# NRF52840.net
KiCad netlist of a schematic drawn in Altium Designer
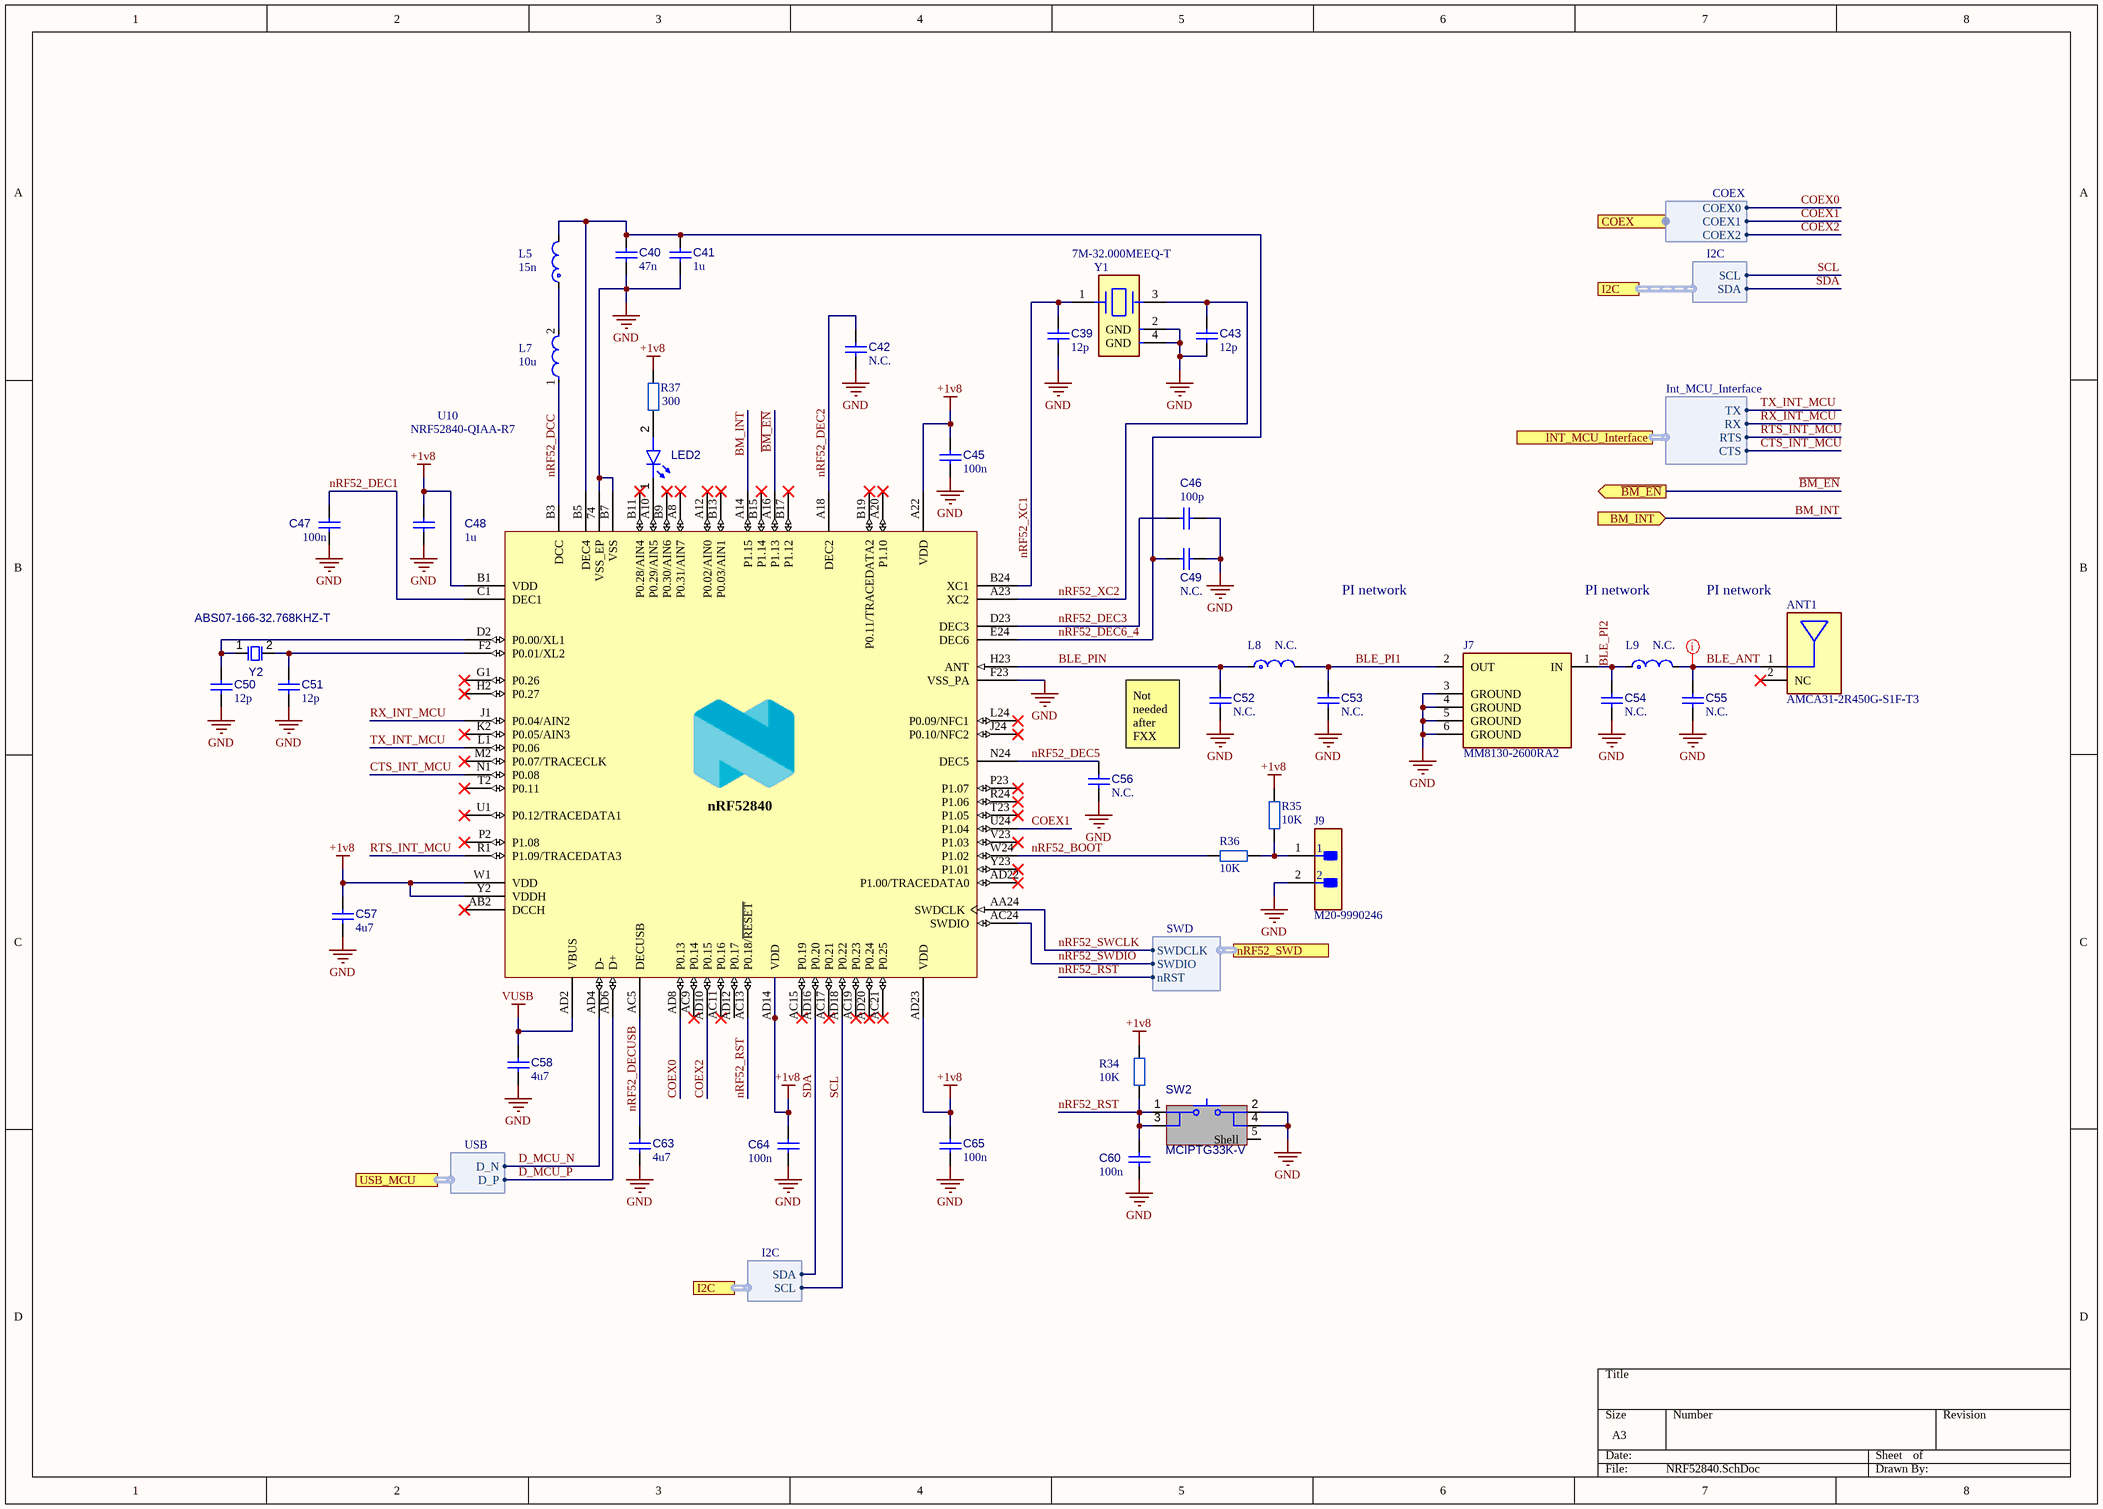
[diagram p0: NRF52840.SchDoc]

(export (version "E")
  (design (tool "Eeschema 10.0.6"))
  (components
    (comp (ref "ANT1")
      (value "AMCA31-2R450G-S1F-T3")
      (footprint "FP-AMCA31-MFG")
      (description "RF ANT 2.4GHZ CHIP SOLDER SMD")
      (fields
        (field (name "OCTOPART") "https://octopart.com/amca31-2r450g-s1f-t3-abracon-31435383")
        (field (name "MANUFACTURER") "Abracon")
      )
      (libsource (lib "Altium Content Vault") (part "feefd54aed95757a858c12fc87bd8d5"))
    )
    (comp (ref "C39")
      (value "12p")
      (footprint "CAPC1005X55X25LL05T10 HD")
      (description "Chip Capacitor, 0402 (1005 Metric)")
      (fields (field (name "TOLERANCE") "?%") (field (name "Comment") "Capacitor 0402"))
      (libsource (lib "Motonaut") (part "CAP-NP-2"))
    )
    (comp (ref "C40")
      (value "47n")
      (footprint "CAPC1005X55X25LL05T10 HD")
      (description "Chip Capacitor, 0402 (1005 Metric)")
      (fields (field (name "TOLERANCE") "?%") (field (name "Comment") "Capacitor 0402"))
      (libsource (lib "Motonaut") (part "CAP-NP-2"))
    )
    (comp (ref "C41")
      (value "1u")
      (footprint "CAPC1005X55X25LL05T10 HD")
      (description "Chip Capacitor, 0402 (1005 Metric)")
      (fields (field (name "TOLERANCE") "?%") (field (name "Comment") "Capacitor 0402"))
      (libsource (lib "Motonaut") (part "CAP-NP-2"))
    )
    (comp (ref "C42")
      (value "N.C.")
      (footprint "CAPC1005X55X25LL05T10 HD")
      (description "Chip Capacitor, 0402 (1005 Metric)")
      (fields (field (name "TOLERANCE") "?%") (field (name "Comment") "Capacitor 0402"))
      (libsource (lib "Motonaut") (part "CAP-NP-2"))
    )
    (comp (ref "C43")
      (value "12p")
      (footprint "CAPC1005X55X25LL05T10 HD")
      (description "Chip Capacitor, 0402 (1005 Metric)")
      (fields (field (name "TOLERANCE") "?%") (field (name "Comment") "Capacitor 0402"))
      (libsource (lib "Motonaut") (part "CAP-NP-2"))
    )
    (comp (ref "C45")
      (value "100n")
      (footprint "CAPC1005X55X25LL05T10 HD")
      (description "Chip Capacitor, 0402 (1005 Metric)")
      (fields (field (name "TOLERANCE") "?%") (field (name "Comment") "Capacitor 0402"))
      (libsource (lib "Motonaut") (part "CAP-NP-2"))
    )
    (comp (ref "C46")
      (value "100p")
      (footprint "CAPC1005X55X25LL05T10 HD")
      (description "Chip Capacitor, 0402 (1005 Metric)")
      (fields (field (name "TOLERANCE") "?%") (field (name "Comment") "Capacitor 0402"))
      (libsource (lib "Motonaut") (part "CAP-NP-2"))
    )
    (comp (ref "C47")
      (value "100n")
      (footprint "CAPC1005X55X25LL05T10 HD")
      (description "Chip Capacitor, 0402 (1005 Metric)")
      (fields (field (name "TOLERANCE") "?%") (field (name "Comment") "Capacitor 0402"))
      (libsource (lib "Motonaut") (part "CAP-NP-2"))
    )
    (comp (ref "C48")
      (value "1u")
      (footprint "CAPC1005X55X25LL05T10 HD")
      (description "Chip Capacitor, 0402 (1005 Metric)")
      (fields (field (name "TOLERANCE") "?%") (field (name "Comment") "Capacitor 0402"))
      (libsource (lib "Motonaut") (part "CAP-NP-2"))
    )
    (comp (ref "C49")
      (value "N.C.")
      (footprint "CAPC1005X55X25LL05T10 HD")
      (description "Chip Capacitor, 0402 (1005 Metric)")
      (fields (field (name "TOLERANCE") "?%") (field (name "Comment") "Capacitor 0402"))
      (libsource (lib "Motonaut") (part "CAP-NP-2"))
    )
    (comp (ref "C50")
      (value "12p")
      (footprint "CAPC1005X55X25LL05T10 HD")
      (description "Chip Capacitor, 0402 (1005 Metric)")
      (fields (field (name "TOLERANCE") "?%") (field (name "Comment") "Capacitor 0402"))
      (libsource (lib "Motonaut") (part "CAP-NP-2"))
    )
    (comp (ref "C51")
      (value "12p")
      (footprint "CAPC1005X55X25LL05T10 HD")
      (description "Chip Capacitor, 0402 (1005 Metric)")
      (fields (field (name "TOLERANCE") "?%") (field (name "Comment") "Capacitor 0402"))
      (libsource (lib "Motonaut") (part "CAP-NP-2"))
    )
    (comp (ref "C52")
      (value "N.C.")
      (footprint "CAPC1005X55X25LL05T10 HD")
      (description "Chip Capacitor, 0402 (1005 Metric)")
      (fields (field (name "TOLERANCE") "?%") (field (name "Comment") "Capacitor 0402"))
      (libsource (lib "Motonaut") (part "CAP-NP-2"))
    )
    (comp (ref "C53")
      (value "N.C.")
      (footprint "CAPC1005X55X25LL05T10 HD")
      (description "Chip Capacitor, 0402 (1005 Metric)")
      (fields (field (name "TOLERANCE") "?%") (field (name "Comment") "Capacitor 0402"))
      (libsource (lib "Motonaut") (part "CAP-NP-2"))
    )
    (comp (ref "C54")
      (value "N.C.")
      (footprint "CAPC1005X55X25LL05T10 HD")
      (description "Chip Capacitor, 0402 (1005 Metric)")
      (fields (field (name "TOLERANCE") "?%") (field (name "Comment") "Capacitor 0402"))
      (libsource (lib "Motonaut") (part "CAP-NP-2"))
    )
    (comp (ref "C55")
      (value "N.C.")
      (footprint "CAPC1005X55X25LL05T10 HD")
      (description "Chip Capacitor, 0402 (1005 Metric)")
      (fields (field (name "TOLERANCE") "?%") (field (name "Comment") "Capacitor 0402"))
      (libsource (lib "Motonaut") (part "CAP-NP-2"))
    )
    (comp (ref "C56")
      (value "N.C.")
      (footprint "CAPC1005X55X25LL05T10 HD")
      (description "Chip Capacitor, 0402 (1005 Metric)")
      (fields (field (name "TOLERANCE") "?%") (field (name "Comment") "Capacitor 0402"))
      (libsource (lib "Motonaut") (part "CAP-NP-2"))
    )
    (comp (ref "C57")
      (value "4u7")
      (footprint "CAPC1005X55X25LL05T10 HD")
      (description "Chip Capacitor, 0402 (1005 Metric)")
      (fields (field (name "TOLERANCE") "?%") (field (name "Comment") "Capacitor 0402"))
      (libsource (lib "Motonaut") (part "CAP-NP-2"))
    )
    (comp (ref "C58")
      (value "4u7")
      (footprint "CAPC1005X55X25LL05T10 HD")
      (description "Chip Capacitor, 0402 (1005 Metric)")
      (fields (field (name "TOLERANCE") "?%") (field (name "Comment") "Capacitor 0402"))
      (libsource (lib "Motonaut") (part "CAP-NP-2"))
    )
    (comp (ref "C60")
      (value "100n")
      (footprint "CAPC1005X55X25LL05T10 HD")
      (description "Chip Capacitor, 0402 (1005 Metric)")
      (fields (field (name "TOLERANCE") "?%") (field (name "Comment") "Capacitor 0402"))
      (libsource (lib "Motonaut") (part "CAP-NP-2"))
    )
    (comp (ref "C63")
      (value "4u7")
      (footprint "CAPC1005X55X25LL05T10 HD")
      (description "Chip Capacitor, 0402 (1005 Metric)")
      (fields (field (name "TOLERANCE") "?%") (field (name "Comment") "Capacitor 0402"))
      (libsource (lib "Motonaut") (part "CAP-NP-2"))
    )
    (comp (ref "C64")
      (value "100n")
      (footprint "CAPC1005X55X25LL05T10 HD")
      (description "Chip Capacitor, 0402 (1005 Metric)")
      (fields (field (name "TOLERANCE") "?%") (field (name "Comment") "Capacitor 0402"))
      (libsource (lib "Motonaut") (part "CAP-NP-2"))
    )
    (comp (ref "C65")
      (value "100n")
      (footprint "CAPC1005X55X25LL05T10 HD")
      (description "Chip Capacitor, 0402 (1005 Metric)")
      (fields (field (name "TOLERANCE") "?%") (field (name "Comment") "Capacitor 0402"))
      (libsource (lib "Motonaut") (part "CAP-NP-2"))
    )
    (comp (ref "J7")
      (value "MM8130-2600RA2")
      (footprint "FP-MM8130-2600RA2-MFG")
      (description "CONN SWF JACK STR 50 OHM SMD")
      (libsource (lib "Motonaut") (part "77d6c4703912e83beb04a2353eb46e6"))
    )
    (comp (ref "J9")
      (value "M20-9990246")
      (footprint "FP-M20-9990246-MFG")
      (description "CONN HEADER VERT 2POS 2.54MM")
      (fields
        (field (name "OCTOPART") "https://octopart.com/m20-9990246-harwin-2590635")
        (field (name "MANUFACTURER") "Harwin")
      )
      (libsource (lib "Altium Content Vault") (part "3bc925449376181038e59eaffc5286c"))
    )
    (comp (ref "L5")
      (value "15n")
      (footprint "INDC1005X55X25LL05T10_A")
      (description "Inductor RF Chip Thin Film 0402")
      (fields (field (name "Comment") "Inductor 0402"))
      (libsource (lib "Motonaut") (part "4cc4b267dca4c8e51f7102f422741d8"))
    )
    (comp (ref "L7")
      (value "10u")
      (footprint "FP-LQM18DN_70-MFG")
      (description "Inductor 0603 Multilayer")
      (fields (field (name "Comment") "Inductor 0603"))
      (libsource (lib "Motonaut") (part "725321dda6339637d4d059423bc1c3c"))
    )
    (comp (ref "L8")
      (value "N.C.")
      (footprint "INDC1005X55X25LL05T10_A")
      (description "Inductor RF Chip Thin Film 0402")
      (fields (field (name "Comment") "Inductor 0402"))
      (libsource (lib "Motonaut") (part "4cc4b267dca4c8e51f7102f422741d8"))
    )
    (comp (ref "L9")
      (value "N.C.")
      (footprint "INDC1005X55X25LL05T10_A")
      (description "Inductor RF Chip Thin Film 0402")
      (fields (field (name "Comment") "Inductor 0402"))
      (libsource (lib "Motonaut") (part "4cc4b267dca4c8e51f7102f422741d8"))
    )
    (comp (ref "LED2")
      (value "QBLP595-R")
      (footprint "QTB-QBLP595_V")
      (description "Chip LED 0402, Red, 0.02 A, 2.0 to 2.5 V, -40 to 80 degC, 2-Pin SMD, RoHS, Tape and Reel")
      (libsource (lib "Motonaut") (part "LED-KA-2"))
    )
    (comp (ref "R34")
      (value "10K")
      (footprint "RESC1005X40X25LL10T10 HD")
      (description "Resistor 0403")
      (libsource (lib "Motonaut") (part "Resistor EU"))
    )
    (comp (ref "R35")
      (value "10K")
      (footprint "RESC1005X40X25LL10T10 HD")
      (description "Resistor 0403")
      (libsource (lib "Motonaut") (part "Resistor EU"))
    )
    (comp (ref "R36")
      (value "10K")
      (footprint "RESC1005X40X25LL10T10 HD")
      (description "Resistor 0403")
      (libsource (lib "Motonaut") (part "Resistor EU"))
    )
    (comp (ref "R37")
      (value "300")
      (footprint "RESC1005X40X25LL10T10 HD")
      (description "Resistor 0403")
      (libsource (lib "Motonaut") (part "Resistor EU"))
    )
    (comp (ref "SW2")
      (value "MCIPTG33K-V")
      (footprint "MCIPTG33K-V-Footprint-1")
      (libsource (lib "Motonaut") (part "4 pin button"))
    )
    (comp (ref "U10")
      (value "NRF52840-QIAA-R7")
      (footprint "NRSC-AQFN-73")
      (description "Advanced multi-protocol SoC supporting Bluetooth 5/ANT/ 802.15.4/ 2.4GHz proprietary")
      (libsource (lib "Motonaut") (part "NRSC-NRF52840-AQFN-73"))
    )
    (comp (ref "Y1")
      (value "7M-32.000MEEQ-T")
      (footprint "FP-7M-MFG")
      (description "Crystal 32MHz ±10ppm (Tol) ±10ppm (Stability) 10pF FUND 50Ohm 4-Pin SMD T/R")
      (libsource (lib "Motonaut") (part "41079aabb0e87794b56622915be14ed"))
    )
    (comp (ref "Y2")
      (value "ABS07-166-32.768KHZ-T")
      (footprint "EPSON-FC-135_V")
      (description "Crystal 32.768kHz 10ppm 7pF -40C +85C")
      (libsource (lib "Motonaut") (part "CMP-001-0024-1"))
    )
  )
  (nets
    (net (code "6") (name "+1v8") (class "Default")
      (node (ref "C45") (pin "2") (pinfunction "2_2") (pintype "passive"))
      (node (ref "C48") (pin "2") (pinfunction "2_2") (pintype "passive"))
      (node (ref "C57") (pin "2") (pinfunction "2_2") (pintype "passive"))
      (node (ref "C64") (pin "2") (pinfunction "2_2") (pintype "passive"))
      (node (ref "C65") (pin "2") (pinfunction "2_2") (pintype "passive"))
      (node (ref "R34") (pin "2") (pinfunction "2_2") (pintype "passive"))
      (node (ref "R35") (pin "1") (pinfunction "1_1") (pintype "passive"))
      (node (ref "R37") (pin "1") (pinfunction "1_1") (pintype "passive"))
      (node (ref "U10") (pin "A22") (pinfunction "VDD_A22") (pintype "power_in"))
      (node (ref "U10") (pin "AD14") (pinfunction "VDD_AD14") (pintype "power_in"))
      (node (ref "U10") (pin "AD23") (pinfunction "VDD_AD23") (pintype "power_in"))
      (node (ref "U10") (pin "B1") (pinfunction "VDD_B1") (pintype "power_in"))
      (node (ref "U10") (pin "W1") (pinfunction "VDD_W1") (pintype "power_in"))
      (node (ref "U10") (pin "Y2") (pinfunction "VDDH_Y2") (pintype "power_in"))
    )
    (net (code "7") (name "/BLE_ANT") (class "Default")
      (node (ref "ANT1") (pin "1") (pinfunction "Feed_Point_1") (pintype "passive"))
      (node (ref "C55") (pin "2") (pinfunction "2_2") (pintype "passive"))
      (node (ref "L9") (pin "2") (pinfunction "2_2") (pintype "passive"))
    )
    (net (code "8") (name "/BLE_PI1") (class "Default")
      (node (ref "C53") (pin "2") (pinfunction "2_2") (pintype "passive"))
      (node (ref "J7") (pin "2") (pinfunction "OUT_2") (pintype "passive"))
      (node (ref "L8") (pin "2") (pinfunction "2_2") (pintype "passive"))
    )
    (net (code "9") (name "/BLE_PI2") (class "Default")
      (node (ref "C54") (pin "2") (pinfunction "2_2") (pintype "passive"))
      (node (ref "J7") (pin "1") (pinfunction "IN_1") (pintype "passive"))
      (node (ref "L9") (pin "1") (pinfunction "1_1") (pintype "passive"))
    )
    (net (code "10") (name "/BLE_PIN") (class "Default")
      (node (ref "C52") (pin "2") (pinfunction "2_2") (pintype "passive"))
      (node (ref "L8") (pin "1") (pinfunction "1_1") (pintype "passive"))
      (node (ref "U10") (pin "H23") (pinfunction "ANT_H23") (pintype "input"))
    )
    (net (code "11") (name "/BM_INT") (class "Default")
      (node (ref "U10") (pin "A14") (pinfunction "P1.15_A14") (pintype "bidirectional"))
    )
    (net (code "12") (name "/COEX0") (class "Default")
      (node (ref "U10") (pin "AD8") (pinfunction "P0.13_AD8") (pintype "bidirectional"))
    )
    (net (code "13") (name "/COEX1") (class "Default")
      (node (ref "U10") (pin "U24") (pinfunction "P1.04_U24") (pintype "bidirectional"))
    )
    (net (code "14") (name "/COEX2") (class "Default")
      (node (ref "U10") (pin "AD10") (pinfunction "P0.15_AD10") (pintype "bidirectional"))
    )
    (net (code "15") (name "/CTS_INT_MCU") (class "Default")
      (node (ref "U10") (pin "N1") (pinfunction "P0.08_N1") (pintype "bidirectional"))
    )
    (net (code "16") (name "/D_MCU_N") (class "Default")
      (node (ref "U10") (pin "AD4") (pinfunction "D-_AD4") (pintype "bidirectional"))
    )
    (net (code "17") (name "/D_MCU_P") (class "Default")
      (node (ref "U10") (pin "AD6") (pinfunction "D+_AD6") (pintype "bidirectional"))
    )
    (net (code "18") (name "/RTS_INT_MCU") (class "Default")
      (node (ref "U10") (pin "R1") (pinfunction "P1.09/TRACEDATA3_R1") (pintype "bidirectional"))
    )
    (net (code "19") (name "/RX_INT_MCU") (class "Default")
      (node (ref "U10") (pin "J1") (pinfunction "P0.04/AIN2_J1") (pintype "bidirectional"))
    )
    (net (code "20") (name "/SCL") (class "Default")
      (node (ref "U10") (pin "AD18") (pinfunction "P0.22_AD18") (pintype "bidirectional"))
    )
    (net (code "21") (name "/SDA") (class "Default")
      (node (ref "U10") (pin "AD16") (pinfunction "P0.20_AD16") (pintype "bidirectional"))
    )
    (net (code "22") (name "/TX_INT_MCU") (class "Default")
      (node (ref "U10") (pin "L1") (pinfunction "P0.06_L1") (pintype "bidirectional"))
    )
    (net (code "23") (name "/nRF52_BOOT") (class "Default")
      (node (ref "R36") (pin "2") (pinfunction "2_2") (pintype "passive"))
      (node (ref "U10") (pin "W24") (pinfunction "P1.02_W24") (pintype "bidirectional"))
    )
    (net (code "24") (name "/nRF52_DCC") (class "Default")
      (node (ref "L7") (pin "1") (pinfunction "1_1") (pintype "passive"))
      (node (ref "U10") (pin "B3") (pinfunction "DCC_B3") (pintype "passive"))
    )
    (net (code "25") (name "/nRF52_DEC1") (class "Default")
      (node (ref "C47") (pin "2") (pinfunction "2_2") (pintype "passive"))
      (node (ref "U10") (pin "C1") (pinfunction "DEC1_C1") (pintype "power_in"))
    )
    (net (code "26") (name "/nRF52_DEC2") (class "Default")
      (node (ref "C42") (pin "2") (pinfunction "2_2") (pintype "passive"))
      (node (ref "U10") (pin "A18") (pinfunction "DEC2_A18") (pintype "power_in"))
    )
    (net (code "27") (name "/nRF52_DEC3") (class "Default")
      (node (ref "C46") (pin "2") (pinfunction "2_2") (pintype "passive"))
      (node (ref "U10") (pin "D23") (pinfunction "DEC3_D23") (pintype "power_in"))
    )
    (net (code "28") (name "/nRF52_DEC5") (class "Default")
      (node (ref "C56") (pin "2") (pinfunction "2_2") (pintype "passive"))
      (node (ref "U10") (pin "N24") (pinfunction "DEC5_N24") (pintype "power_in"))
    )
    (net (code "29") (name "/nRF52_DEC6_4") (class "Default")
      (node (ref "C40") (pin "2") (pinfunction "2_2") (pintype "passive"))
      (node (ref "C41") (pin "2") (pinfunction "2_2") (pintype "passive"))
      (node (ref "C49") (pin "2") (pinfunction "2_2") (pintype "passive"))
      (node (ref "L5") (pin "2") (pinfunction "2_2") (pintype "passive"))
      (node (ref "U10") (pin "B5") (pinfunction "DEC4_B5") (pintype "power_in"))
      (node (ref "U10") (pin "E24") (pinfunction "DEC6_E24") (pintype "power_in"))
    )
    (net (code "30") (name "/nRF52_DECUSB") (class "Default")
      (node (ref "C63") (pin "2") (pinfunction "2_2") (pintype "passive"))
      (node (ref "U10") (pin "AC5") (pinfunction "DECUSB_AC5") (pintype "power_in"))
    )
    (net (code "31") (name "/nRF52_RST") (class "Default")
      (node (ref "C60") (pin "2") (pinfunction "2_2") (pintype "passive"))
      (node (ref "R34") (pin "1") (pinfunction "1_1") (pintype "passive"))
      (node (ref "SW2") (pin "1") (pinfunction "1_1") (pintype "passive"))
      (node (ref "SW2") (pin "3") (pinfunction "3_3") (pintype "passive"))
      (node (ref "U10") (pin "AC13") (pinfunction "P0.18/~{RESET}_AC13") (pintype "bidirectional"))
    )
    (net (code "32") (name "/nRF52_SWCLK") (class "Default")
      (node (ref "U10") (pin "AA24") (pinfunction "SWDCLK_AA24") (pintype "input"))
    )
    (net (code "33") (name "/nRF52_SWDIO") (class "Default")
      (node (ref "U10") (pin "AC24") (pinfunction "SWDIO_AC24") (pintype "bidirectional"))
    )
    (net (code "34") (name "/nRF52_XC1") (class "Default")
      (node (ref "C39") (pin "2") (pinfunction "2_2") (pintype "passive"))
      (node (ref "U10") (pin "B24") (pinfunction "XC1_B24") (pintype "passive"))
      (node (ref "Y1") (pin "1") (pinfunction "1_1") (pintype "passive"))
    )
    (net (code "35") (name "/nRF52_XC2") (class "Default")
      (node (ref "C43") (pin "2") (pinfunction "2_2") (pintype "passive"))
      (node (ref "U10") (pin "A23") (pinfunction "XC2_A23") (pintype "passive"))
      (node (ref "Y1") (pin "3") (pinfunction "3_3") (pintype "passive"))
    )
    (net (code "41") (name "/~{BM_EN}") (class "Default")
      (node (ref "U10") (pin "A16") (pinfunction "P1.13_A16") (pintype "bidirectional"))
    )
    (net (code "42") (name "GND") (class "Default")
      (node (ref "C39") (pin "1") (pinfunction "1_1") (pintype "passive"))
      (node (ref "C40") (pin "1") (pinfunction "1_1") (pintype "passive"))
      (node (ref "C41") (pin "1") (pinfunction "1_1") (pintype "passive"))
      (node (ref "C42") (pin "1") (pinfunction "1_1") (pintype "passive"))
      (node (ref "C43") (pin "1") (pinfunction "1_1") (pintype "passive"))
      (node (ref "C45") (pin "1") (pinfunction "1_1") (pintype "passive"))
      (node (ref "C46") (pin "1") (pinfunction "1_1") (pintype "passive"))
      (node (ref "C47") (pin "1") (pinfunction "1_1") (pintype "passive"))
      (node (ref "C48") (pin "1") (pinfunction "1_1") (pintype "passive"))
      (node (ref "C49") (pin "1") (pinfunction "1_1") (pintype "passive"))
      (node (ref "C50") (pin "1") (pinfunction "1_1") (pintype "passive"))
      (node (ref "C51") (pin "1") (pinfunction "1_1") (pintype "passive"))
      (node (ref "C52") (pin "1") (pinfunction "1_1") (pintype "passive"))
      (node (ref "C53") (pin "1") (pinfunction "1_1") (pintype "passive"))
      (node (ref "C54") (pin "1") (pinfunction "1_1") (pintype "passive"))
      (node (ref "C55") (pin "1") (pinfunction "1_1") (pintype "passive"))
      (node (ref "C56") (pin "1") (pinfunction "1_1") (pintype "passive"))
      (node (ref "C57") (pin "1") (pinfunction "1_1") (pintype "passive"))
      (node (ref "C58") (pin "1") (pinfunction "1_1") (pintype "passive"))
      (node (ref "C60") (pin "1") (pinfunction "1_1") (pintype "passive"))
      (node (ref "C63") (pin "1") (pinfunction "1_1") (pintype "passive"))
      (node (ref "C64") (pin "1") (pinfunction "1_1") (pintype "passive"))
      (node (ref "C65") (pin "1") (pinfunction "1_1") (pintype "passive"))
      (node (ref "J7") (pin "3") (pinfunction "GROUND_3") (pintype "power_in"))
      (node (ref "J7") (pin "4") (pinfunction "GROUND_4") (pintype "power_in"))
      (node (ref "J7") (pin "5") (pinfunction "GROUND_5") (pintype "power_in"))
      (node (ref "J7") (pin "6") (pinfunction "GROUND_6") (pintype "power_in"))
      (node (ref "J9") (pin "2") (pinfunction "2_2") (pintype "passive"))
      (node (ref "SW2") (pin "2") (pinfunction "2_2") (pintype "passive"))
      (node (ref "SW2") (pin "4") (pinfunction "4_4") (pintype "passive"))
      (node (ref "U10") (pin "74") (pinfunction "VSS_EP_74") (pintype "power_in"))
      (node (ref "U10") (pin "B7") (pinfunction "VSS_B7") (pintype "power_in"))
      (node (ref "U10") (pin "F23") (pinfunction "VSS_PA_F23") (pintype "power_in"))
      (node (ref "Y1") (pin "2") (pinfunction "GND_2") (pintype "power_in"))
      (node (ref "Y1") (pin "4") (pinfunction "GND_4") (pintype "power_in"))
    )
    (net (code "43") (name "Net-(J9-Pad1)") (class "Default")
      (node (ref "J9") (pin "1") (pinfunction "1_1") (pintype "passive"))
      (node (ref "R35") (pin "2") (pinfunction "2_2") (pintype "passive"))
      (node (ref "R36") (pin "1") (pinfunction "1_1") (pintype "passive"))
    )
    (net (code "44") (name "Net-(L5-Pad1)") (class "Default")
      (node (ref "L5") (pin "1") (pinfunction "1_1") (pintype "passive"))
      (node (ref "L7") (pin "2") (pinfunction "2_2") (pintype "passive"))
    )
    (net (code "45") (name "Net-(LED2-A)") (class "Default")
      (node (ref "LED2") (pin "2") (pinfunction "A_2") (pintype "passive"))
      (node (ref "R37") (pin "2") (pinfunction "2_2") (pintype "passive"))
    )
    (net (code "46") (name "Net-(LED2-K)") (class "Default")
      (node (ref "LED2") (pin "1") (pinfunction "K_1") (pintype "passive"))
      (node (ref "U10") (pin "A10") (pinfunction "P0.29/AIN5_A10") (pintype "bidirectional"))
    )
    (net (code "47") (name "Net-(U10-P0.00{slash}XL1)") (class "Default")
      (node (ref "C50") (pin "2") (pinfunction "2_2") (pintype "passive"))
      (node (ref "U10") (pin "D2") (pinfunction "P0.00/XL1_D2") (pintype "bidirectional"))
      (node (ref "Y2") (pin "1") (pinfunction "1_1") (pintype "passive"))
    )
    (net (code "48") (name "Net-(U10-P0.01{slash}XL2)") (class "Default")
      (node (ref "C51") (pin "2") (pinfunction "2_2") (pintype "passive"))
      (node (ref "U10") (pin "F2") (pinfunction "P0.01/XL2_F2") (pintype "bidirectional"))
      (node (ref "Y2") (pin "2") (pinfunction "2_2") (pintype "passive"))
    )
    (net (code "49") (name "VUSB") (class "Default")
      (node (ref "C58") (pin "2") (pinfunction "2_2") (pintype "passive"))
      (node (ref "U10") (pin "AD2") (pinfunction "VBUS_AD2") (pintype "power_in"))
    )
    (net (code "50") (name "unconnected-(ANT1-NC-Pad2)") (class "Default")
      (node (ref "ANT1") (pin "2") (pinfunction "NC_2") (pintype "passive+no_connect"))
    )
    (net (code "51") (name "unconnected-(SW2-Shell-Pad5)") (class "Default")
      (node (ref "SW2") (pin "5") (pinfunction "Shell_5") (pintype "passive"))
    )
    (net (code "52") (name "unconnected-(U10-DCCH-PadAB2)") (class "Default")
      (node (ref "U10") (pin "AB2") (pinfunction "DCCH_AB2") (pintype "power_in+no_connect"))
    )
    (net (code "53") (name "unconnected-(U10-P0.02{slash}AIN0-PadA12)") (class "Default")
      (node (ref "U10") (pin "A12") (pinfunction "P0.02/AIN0_A12") (pintype "bidirectional+no_connect"))
    )
    (net (code "54") (name "unconnected-(U10-P0.03{slash}AIN1-PadB13)") (class "Default")
      (node (ref "U10") (pin "B13") (pinfunction "P0.03/AIN1_B13") (pintype "bidirectional+no_connect"))
    )
    (net (code "55") (name "unconnected-(U10-P0.05{slash}AIN3-PadK2)") (class "Default")
      (node (ref "U10") (pin "K2") (pinfunction "P0.05/AIN3_K2") (pintype "bidirectional+no_connect"))
    )
    (net (code "56") (name "unconnected-(U10-P0.07{slash}TRACECLK-PadM2)") (class "Default")
      (node (ref "U10") (pin "M2") (pinfunction "P0.07/TRACECLK_M2") (pintype "bidirectional+no_connect"))
    )
    (net (code "57") (name "unconnected-(U10-P0.09{slash}NFC1-PadL24)") (class "Default")
      (node (ref "U10") (pin "L24") (pinfunction "P0.09/NFC1_L24") (pintype "bidirectional+no_connect"))
    )
    (net (code "58") (name "unconnected-(U10-P0.10{slash}NFC2-PadJ24)") (class "Default")
      (node (ref "U10") (pin "J24") (pinfunction "P0.10/NFC2_J24") (pintype "bidirectional+no_connect"))
    )
    (net (code "59") (name "unconnected-(U10-P0.11-PadT2)") (class "Default")
      (node (ref "U10") (pin "T2") (pinfunction "P0.11_T2") (pintype "bidirectional+no_connect"))
    )
    (net (code "60") (name "unconnected-(U10-P0.11{slash}TRACEDATA2-PadB19)") (class "Default")
      (node (ref "U10") (pin "B19") (pinfunction "P0.11/TRACEDATA2_B19") (pintype "bidirectional+no_connect"))
    )
    (net (code "61") (name "unconnected-(U10-P0.12{slash}TRACEDATA1-PadU1)") (class "Default")
      (node (ref "U10") (pin "U1") (pinfunction "P0.12/TRACEDATA1_U1") (pintype "bidirectional+no_connect"))
    )
    (net (code "62") (name "unconnected-(U10-P0.14-PadAC9)") (class "Default")
      (node (ref "U10") (pin "AC9") (pinfunction "P0.14_AC9") (pintype "bidirectional+no_connect"))
    )
    (net (code "63") (name "unconnected-(U10-P0.16-PadAC11)") (class "Default")
      (node (ref "U10") (pin "AC11") (pinfunction "P0.16_AC11") (pintype "bidirectional+no_connect"))
    )
    (net (code "64") (name "unconnected-(U10-P0.17-PadAD12)") (class "Default")
      (node (ref "U10") (pin "AD12") (pinfunction "P0.17_AD12") (pintype "bidirectional"))
    )
    (net (code "65") (name "unconnected-(U10-P0.19-PadAC15)") (class "Default")
      (node (ref "U10") (pin "AC15") (pinfunction "P0.19_AC15") (pintype "bidirectional+no_connect"))
    )
    (net (code "66") (name "unconnected-(U10-P0.21-PadAC17)") (class "Default")
      (node (ref "U10") (pin "AC17") (pinfunction "P0.21_AC17") (pintype "bidirectional+no_connect"))
    )
    (net (code "67") (name "unconnected-(U10-P0.23-PadAC19)") (class "Default")
      (node (ref "U10") (pin "AC19") (pinfunction "P0.23_AC19") (pintype "bidirectional+no_connect"))
    )
    (net (code "68") (name "unconnected-(U10-P0.24-PadAD20)") (class "Default")
      (node (ref "U10") (pin "AD20") (pinfunction "P0.24_AD20") (pintype "bidirectional+no_connect"))
    )
    (net (code "69") (name "unconnected-(U10-P0.25-PadAC21)") (class "Default")
      (node (ref "U10") (pin "AC21") (pinfunction "P0.25_AC21") (pintype "bidirectional+no_connect"))
    )
    (net (code "70") (name "unconnected-(U10-P0.26-PadG1)") (class "Default")
      (node (ref "U10") (pin "G1") (pinfunction "P0.26_G1") (pintype "bidirectional+no_connect"))
    )
    (net (code "71") (name "unconnected-(U10-P0.27-PadH2)") (class "Default")
      (node (ref "U10") (pin "H2") (pinfunction "P0.27_H2") (pintype "bidirectional+no_connect"))
    )
    (net (code "72") (name "unconnected-(U10-P0.28{slash}AIN4-PadB11)") (class "Default")
      (node (ref "U10") (pin "B11") (pinfunction "P0.28/AIN4_B11") (pintype "bidirectional+no_connect"))
    )
    (net (code "73") (name "unconnected-(U10-P0.30{slash}AIN6-PadB9)") (class "Default")
      (node (ref "U10") (pin "B9") (pinfunction "P0.30/AIN6_B9") (pintype "bidirectional+no_connect"))
    )
    (net (code "74") (name "unconnected-(U10-P0.31{slash}AIN7-PadA8)") (class "Default")
      (node (ref "U10") (pin "A8") (pinfunction "P0.31/AIN7_A8") (pintype "bidirectional+no_connect"))
    )
    (net (code "75") (name "unconnected-(U10-P1.00{slash}TRACEDATA0-PadAD22)") (class "Default")
      (node (ref "U10") (pin "AD22") (pinfunction "P1.00/TRACEDATA0_AD22") (pintype "bidirectional+no_connect"))
    )
    (net (code "76") (name "unconnected-(U10-P1.01-PadY23)") (class "Default")
      (node (ref "U10") (pin "Y23") (pinfunction "P1.01_Y23") (pintype "bidirectional+no_connect"))
    )
    (net (code "77") (name "unconnected-(U10-P1.03-PadV23)") (class "Default")
      (node (ref "U10") (pin "V23") (pinfunction "P1.03_V23") (pintype "bidirectional+no_connect"))
    )
    (net (code "78") (name "unconnected-(U10-P1.05-PadT23)") (class "Default")
      (node (ref "U10") (pin "T23") (pinfunction "P1.05_T23") (pintype "bidirectional+no_connect"))
    )
    (net (code "79") (name "unconnected-(U10-P1.06-PadR24)") (class "Default")
      (node (ref "U10") (pin "R24") (pinfunction "P1.06_R24") (pintype "bidirectional+no_connect"))
    )
    (net (code "80") (name "unconnected-(U10-P1.07-PadP23)") (class "Default")
      (node (ref "U10") (pin "P23") (pinfunction "P1.07_P23") (pintype "bidirectional+no_connect"))
    )
    (net (code "81") (name "unconnected-(U10-P1.08-PadP2)") (class "Default")
      (node (ref "U10") (pin "P2") (pinfunction "P1.08_P2") (pintype "bidirectional+no_connect"))
    )
    (net (code "82") (name "unconnected-(U10-P1.10-PadA20)") (class "Default")
      (node (ref "U10") (pin "A20") (pinfunction "P1.10_A20") (pintype "bidirectional+no_connect"))
    )
    (net (code "83") (name "unconnected-(U10-P1.12-PadB17)") (class "Default")
      (node (ref "U10") (pin "B17") (pinfunction "P1.12_B17") (pintype "bidirectional+no_connect"))
    )
    (net (code "84") (name "unconnected-(U10-P1.14-PadB15)") (class "Default")
      (node (ref "U10") (pin "B15") (pinfunction "P1.14_B15") (pintype "bidirectional+no_connect"))
    )
  )
)
